# Valve_Driver_V4_1.net
KiCad netlist of a schematic drawn in EAGLE
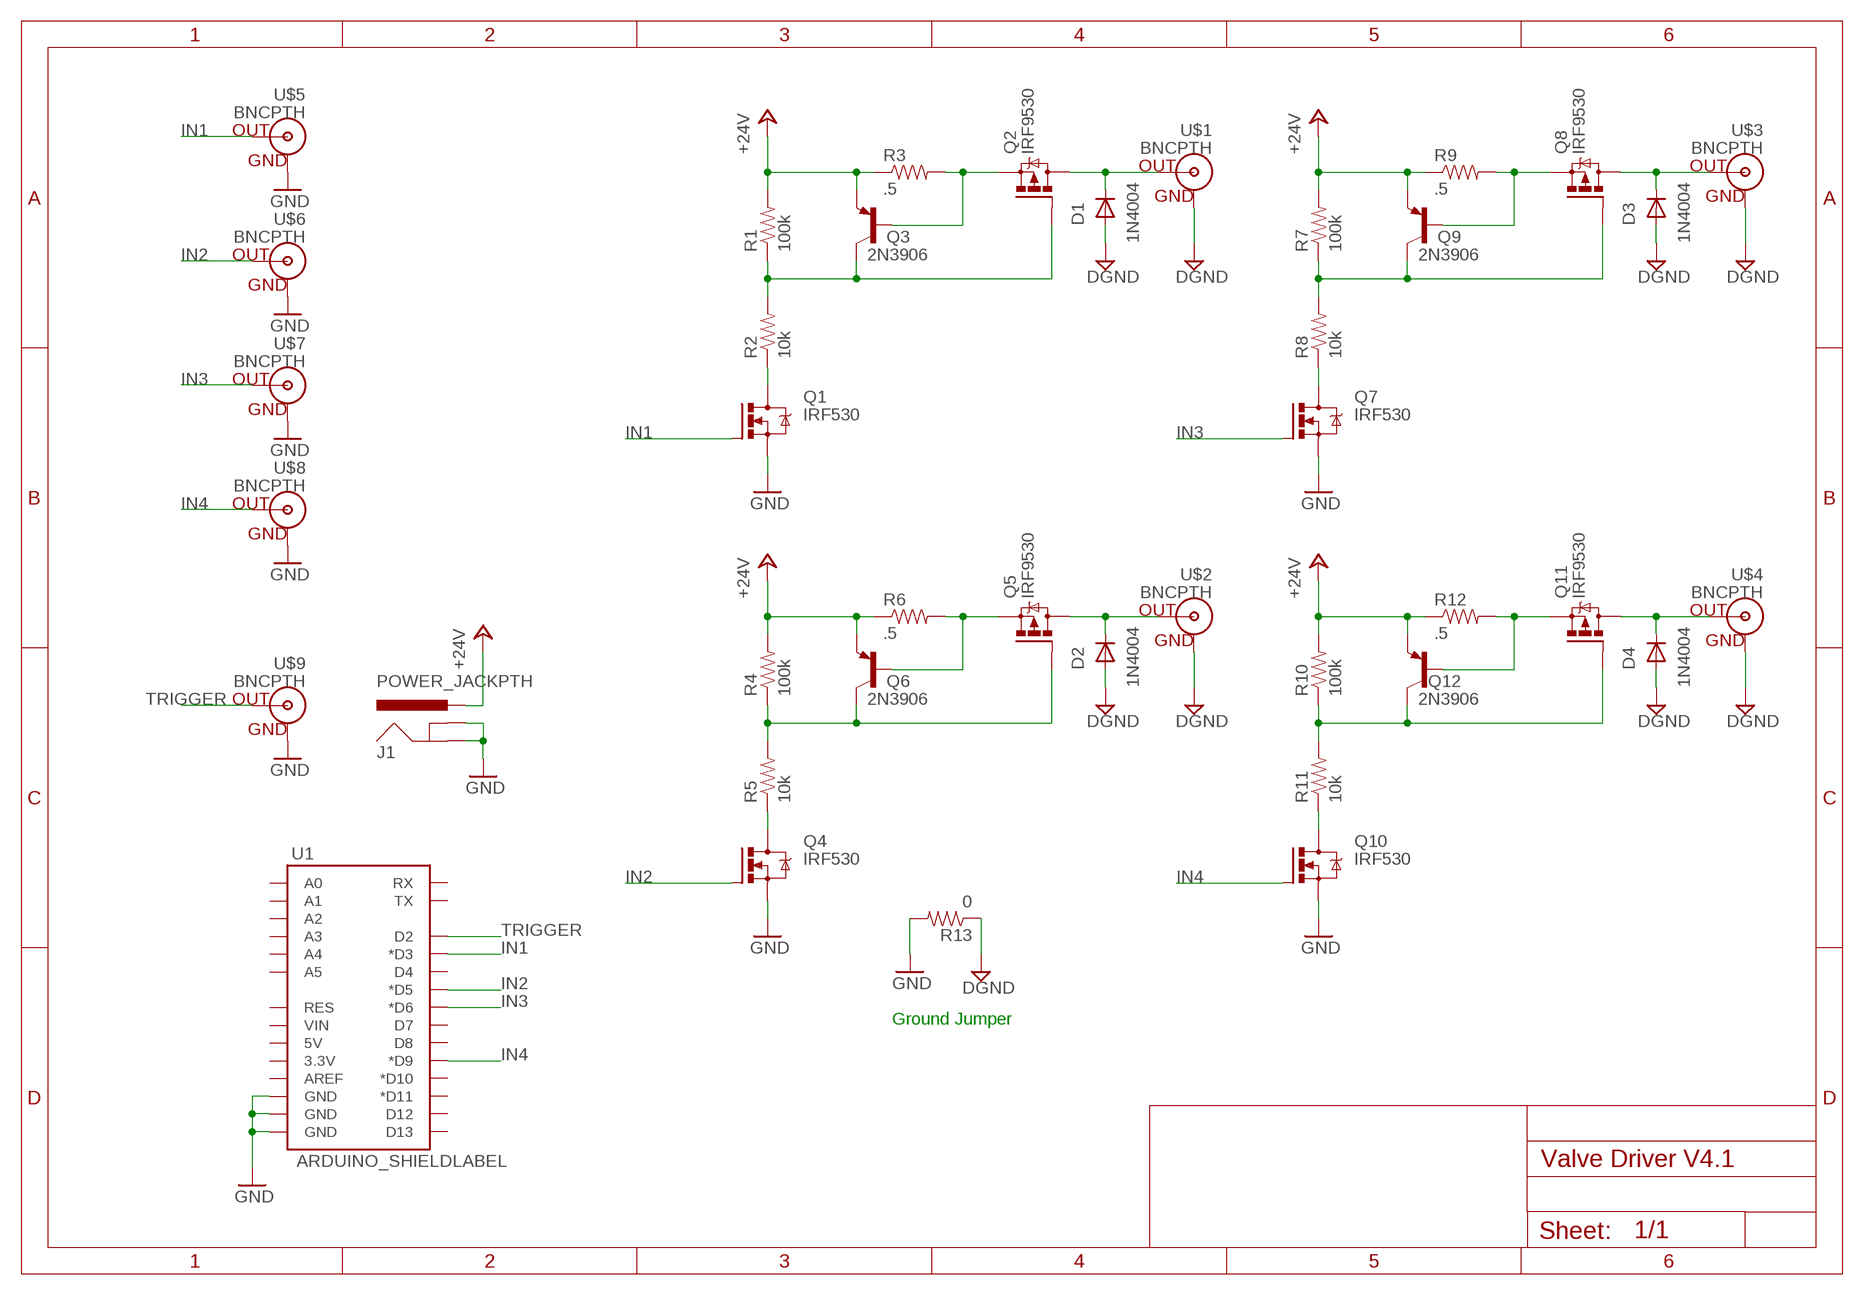
[diagram p0: schematic, sheet 1]

(export (version "E")
  (design (tool "Eeschema 10.0.6"))
  (components
    (comp (ref "D1")
      (value "1N4004")
      (footprint "eagle-import:DO41-10")
      (libsource (lib "eagle-import") (part "1N4004"))
    )
    (comp (ref "D2")
      (value "1N4004")
      (footprint "eagle-import:DO41-10")
      (libsource (lib "eagle-import") (part "1N4004"))
    )
    (comp (ref "D3")
      (value "1N4004")
      (footprint "eagle-import:DO41-10")
      (libsource (lib "eagle-import") (part "1N4004"))
    )
    (comp (ref "D4")
      (value "1N4004")
      (footprint "eagle-import:DO41-10")
      (libsource (lib "eagle-import") (part "1N4004"))
    )
    (comp (ref "J1")
      (value "POWER_JACKPTH")
      (footprint "eagle-import:POWER_JACK_PTH")
      (libsource (lib "eagle-import") (part "POWER_JACKPTH"))
    )
    (comp (ref "Q1")
      (value "IRF530")
      (footprint "eagle-import:TO220BV")
      (libsource (lib "eagle-import") (part "IRF530TO220"))
    )
    (comp (ref "Q2")
      (value "IRF9530")
      (footprint "eagle-import:TO220BV")
      (libsource (lib "eagle-import") (part "IRF9530"))
    )
    (comp (ref "Q3")
      (value "2N3906")
      (footprint "eagle-import:TO92")
      (libsource (lib "eagle-import") (part "2N3906"))
    )
    (comp (ref "Q4")
      (value "IRF530")
      (footprint "eagle-import:TO220BV")
      (libsource (lib "eagle-import") (part "IRF530TO220"))
    )
    (comp (ref "Q5")
      (value "IRF9530")
      (footprint "eagle-import:TO220BV")
      (libsource (lib "eagle-import") (part "IRF9530"))
    )
    (comp (ref "Q6")
      (value "2N3906")
      (footprint "eagle-import:TO92")
      (libsource (lib "eagle-import") (part "2N3906"))
    )
    (comp (ref "Q7")
      (value "IRF530")
      (footprint "eagle-import:TO220BV")
      (libsource (lib "eagle-import") (part "IRF530TO220"))
    )
    (comp (ref "Q8")
      (value "IRF9530")
      (footprint "eagle-import:TO220BV")
      (libsource (lib "eagle-import") (part "IRF9530"))
    )
    (comp (ref "Q9")
      (value "2N3906")
      (footprint "eagle-import:TO92")
      (libsource (lib "eagle-import") (part "2N3906"))
    )
    (comp (ref "Q10")
      (value "IRF530")
      (footprint "eagle-import:TO220BV")
      (libsource (lib "eagle-import") (part "IRF530TO220"))
    )
    (comp (ref "Q11")
      (value "IRF9530")
      (footprint "eagle-import:TO220BV")
      (libsource (lib "eagle-import") (part "IRF9530"))
    )
    (comp (ref "Q12")
      (value "2N3906")
      (footprint "eagle-import:TO92")
      (libsource (lib "eagle-import") (part "2N3906"))
    )
    (comp (ref "R1")
      (value "100k")
      (footprint "eagle-import:AXIAL-0.4")
      (libsource (lib "eagle-import") (part "RESISTORPTH-1/4W"))
    )
    (comp (ref "R2")
      (value "10k")
      (footprint "eagle-import:AXIAL-0.4")
      (libsource (lib "eagle-import") (part "RESISTORPTH-1/4W"))
    )
    (comp (ref "R3")
      (value ".5")
      (footprint "eagle-import:AXIAL-0.4")
      (libsource (lib "eagle-import") (part "RESISTORPTH-1/4W"))
    )
    (comp (ref "R4")
      (value "100k")
      (footprint "eagle-import:AXIAL-0.4")
      (libsource (lib "eagle-import") (part "RESISTORPTH-1/4W"))
    )
    (comp (ref "R5")
      (value "10k")
      (footprint "eagle-import:AXIAL-0.4")
      (libsource (lib "eagle-import") (part "RESISTORPTH-1/4W"))
    )
    (comp (ref "R6")
      (value ".5")
      (footprint "eagle-import:AXIAL-0.4")
      (libsource (lib "eagle-import") (part "RESISTORPTH-1/4W"))
    )
    (comp (ref "R7")
      (value "100k")
      (footprint "eagle-import:AXIAL-0.4")
      (libsource (lib "eagle-import") (part "RESISTORPTH-1/4W"))
    )
    (comp (ref "R8")
      (value "10k")
      (footprint "eagle-import:AXIAL-0.4")
      (libsource (lib "eagle-import") (part "RESISTORPTH-1/4W"))
    )
    (comp (ref "R9")
      (value ".5")
      (footprint "eagle-import:AXIAL-0.4")
      (libsource (lib "eagle-import") (part "RESISTORPTH-1/4W"))
    )
    (comp (ref "R10")
      (value "100k")
      (footprint "eagle-import:AXIAL-0.4")
      (libsource (lib "eagle-import") (part "RESISTORPTH-1/4W"))
    )
    (comp (ref "R11")
      (value "10k")
      (footprint "eagle-import:AXIAL-0.4")
      (libsource (lib "eagle-import") (part "RESISTORPTH-1/4W"))
    )
    (comp (ref "R12")
      (value ".5")
      (footprint "eagle-import:AXIAL-0.4")
      (libsource (lib "eagle-import") (part "RESISTORPTH-1/4W"))
    )
    (comp (ref "R13")
      (value "0")
      (footprint "eagle-import:AXIAL-0.4")
      (libsource (lib "eagle-import") (part "RESISTORPTH-1/4W"))
    )
    (comp (ref "U$1")
      (value "BNCPTH")
      (footprint "eagle-import:BNC")
      (libsource (lib "eagle-import") (part "BNCPTH"))
    )
    (comp (ref "U$2")
      (value "BNCPTH")
      (footprint "eagle-import:BNC")
      (libsource (lib "eagle-import") (part "BNCPTH"))
    )
    (comp (ref "U$3")
      (value "BNCPTH")
      (footprint "eagle-import:BNC")
      (libsource (lib "eagle-import") (part "BNCPTH"))
    )
    (comp (ref "U$4")
      (value "BNCPTH")
      (footprint "eagle-import:BNC")
      (libsource (lib "eagle-import") (part "BNCPTH"))
    )
    (comp (ref "U$5")
      (value "BNCPTH")
      (footprint "eagle-import:BNC")
      (libsource (lib "eagle-import") (part "BNCPTH"))
    )
    (comp (ref "U$6")
      (value "BNCPTH")
      (footprint "eagle-import:BNC")
      (libsource (lib "eagle-import") (part "BNCPTH"))
    )
    (comp (ref "U$7")
      (value "BNCPTH")
      (footprint "eagle-import:BNC")
      (libsource (lib "eagle-import") (part "BNCPTH"))
    )
    (comp (ref "U$8")
      (value "BNCPTH")
      (footprint "eagle-import:BNC")
      (libsource (lib "eagle-import") (part "BNCPTH"))
    )
    (comp (ref "U$9")
      (value "BNCPTH")
      (footprint "eagle-import:BNC")
      (libsource (lib "eagle-import") (part "BNCPTH"))
    )
    (comp (ref "U1")
      (value "ARDUINO_SHIELDLABEL")
      (footprint "eagle-import:DUEMILANOVE_SHIELD")
      (libsource (lib "eagle-import") (part "ARDUINO_SHIELDLABEL"))
    )
  )
  (nets
    (net (code "1") (name "+24V") (class "Default")
      (node (ref "J1") (pin "PWR") (pinfunction "PWR_PWR") (pintype "bidirectional"))
      (node (ref "Q12") (pin "3") (pinfunction "E_3") (pintype "passive"))
      (node (ref "Q3") (pin "3") (pinfunction "E_3") (pintype "passive"))
      (node (ref "Q6") (pin "3") (pinfunction "E_3") (pintype "passive"))
      (node (ref "Q9") (pin "3") (pinfunction "E_3") (pintype "passive"))
      (node (ref "R1") (pin "P$2") (pinfunction "2_P$2") (pintype "passive"))
      (node (ref "R10") (pin "P$2") (pinfunction "2_P$2") (pintype "passive"))
      (node (ref "R12") (pin "P$1") (pinfunction "1_P$1") (pintype "passive"))
      (node (ref "R3") (pin "P$1") (pinfunction "1_P$1") (pintype "passive"))
      (node (ref "R4") (pin "P$2") (pinfunction "2_P$2") (pintype "passive"))
      (node (ref "R6") (pin "P$1") (pinfunction "1_P$1") (pintype "passive"))
      (node (ref "R7") (pin "P$2") (pinfunction "2_P$2") (pintype "passive"))
      (node (ref "R9") (pin "P$1") (pinfunction "1_P$1") (pintype "passive"))
    )
    (net (code "2") (name "/IN1") (class "Default")
      (node (ref "Q1") (pin "G") (pinfunction "G_G") (pintype "passive"))
      (node (ref "U$5") (pin "S") (pinfunction "OUT_S") (pintype "bidirectional"))
      (node (ref "U1") (pin "D3") (pinfunction "*D3_D3") (pintype "bidirectional"))
    )
    (net (code "3") (name "/IN2") (class "Default")
      (node (ref "Q4") (pin "G") (pinfunction "G_G") (pintype "passive"))
      (node (ref "U$6") (pin "S") (pinfunction "OUT_S") (pintype "bidirectional"))
      (node (ref "U1") (pin "D5") (pinfunction "*D5_D5") (pintype "bidirectional"))
    )
    (net (code "4") (name "/IN3") (class "Default")
      (node (ref "Q7") (pin "G") (pinfunction "G_G") (pintype "passive"))
      (node (ref "U$7") (pin "S") (pinfunction "OUT_S") (pintype "bidirectional"))
      (node (ref "U1") (pin "D6") (pinfunction "*D6_D6") (pintype "bidirectional"))
    )
    (net (code "5") (name "/IN4") (class "Default")
      (node (ref "Q10") (pin "G") (pinfunction "G_G") (pintype "passive"))
      (node (ref "U$8") (pin "S") (pinfunction "OUT_S") (pintype "bidirectional"))
      (node (ref "U1") (pin "D9") (pinfunction "*D9_D9") (pintype "bidirectional"))
    )
    (net (code "6") (name "/TRIGGER") (class "Default")
      (node (ref "U$9") (pin "S") (pinfunction "OUT_S") (pintype "bidirectional"))
      (node (ref "U1") (pin "D2") (pinfunction "D2_D2") (pintype "bidirectional"))
    )
    (net (code "7") (name "DGND") (class "Default")
      (node (ref "D1") (pin "A") (pinfunction "A_A") (pintype "passive"))
      (node (ref "D2") (pin "A") (pinfunction "A_A") (pintype "passive"))
      (node (ref "D3") (pin "A") (pinfunction "A_A") (pintype "passive"))
      (node (ref "D4") (pin "A") (pinfunction "A_A") (pintype "passive"))
      (node (ref "R13") (pin "P$1") (pinfunction "1_P$1") (pintype "passive"))
      (node (ref "U$1") (pin "GND") (pinfunction "GND_GND") (pintype "bidirectional"))
      (node (ref "U$2") (pin "GND") (pinfunction "GND_GND") (pintype "bidirectional"))
      (node (ref "U$3") (pin "GND") (pinfunction "GND_GND") (pintype "bidirectional"))
      (node (ref "U$4") (pin "GND") (pinfunction "GND_GND") (pintype "bidirectional"))
    )
    (net (code "8") (name "GND") (class "Default")
      (node (ref "J1") (pin "GND") (pinfunction "GND_GND") (pintype "bidirectional"))
      (node (ref "J1") (pin "GNDBREAK") (pinfunction "GNDBREAK_GNDBREAK") (pintype "bidirectional"))
      (node (ref "Q1") (pin "S") (pinfunction "S_S") (pintype "passive"))
      (node (ref "Q10") (pin "S") (pinfunction "S_S") (pintype "passive"))
      (node (ref "Q4") (pin "S") (pinfunction "S_S") (pintype "passive"))
      (node (ref "Q7") (pin "S") (pinfunction "S_S") (pintype "passive"))
      (node (ref "R13") (pin "P$2") (pinfunction "2_P$2") (pintype "passive"))
      (node (ref "U$5") (pin "GND") (pinfunction "GND_GND") (pintype "bidirectional"))
      (node (ref "U$6") (pin "GND") (pinfunction "GND_GND") (pintype "bidirectional"))
      (node (ref "U$7") (pin "GND") (pinfunction "GND_GND") (pintype "bidirectional"))
      (node (ref "U$8") (pin "GND") (pinfunction "GND_GND") (pintype "bidirectional"))
      (node (ref "U$9") (pin "GND") (pinfunction "GND_GND") (pintype "bidirectional"))
      (node (ref "U1") (pin "GND@0") (pinfunction "GND_GND@0") (pintype "bidirectional"))
      (node (ref "U1") (pin "GND@1") (pinfunction "GND_GND@1") (pintype "bidirectional"))
      (node (ref "U1") (pin "GND@2") (pinfunction "GND_GND@2") (pintype "bidirectional"))
    )
    (net (code "9") (name "Net-(Q3-B)") (class "Default")
      (node (ref "Q2") (pin "S") (pinfunction "S_S") (pintype "passive"))
      (node (ref "Q3") (pin "2") (pinfunction "B_2") (pintype "passive"))
      (node (ref "R3") (pin "P$2") (pinfunction "2_P$2") (pintype "passive"))
    )
    (net (code "10") (name "Net-(Q3-C)") (class "Default")
      (node (ref "Q2") (pin "G") (pinfunction "G_G") (pintype "passive"))
      (node (ref "Q3") (pin "1") (pinfunction "C_1") (pintype "passive"))
      (node (ref "R1") (pin "P$1") (pinfunction "1_P$1") (pintype "passive"))
      (node (ref "R2") (pin "P$2") (pinfunction "2_P$2") (pintype "passive"))
    )
    (net (code "11") (name "Net-(Q6-B)") (class "Default")
      (node (ref "Q5") (pin "S") (pinfunction "S_S") (pintype "passive"))
      (node (ref "Q6") (pin "2") (pinfunction "B_2") (pintype "passive"))
      (node (ref "R6") (pin "P$2") (pinfunction "2_P$2") (pintype "passive"))
    )
    (net (code "12") (name "Net-(Q6-C)") (class "Default")
      (node (ref "Q5") (pin "G") (pinfunction "G_G") (pintype "passive"))
      (node (ref "Q6") (pin "1") (pinfunction "C_1") (pintype "passive"))
      (node (ref "R4") (pin "P$1") (pinfunction "1_P$1") (pintype "passive"))
      (node (ref "R5") (pin "P$2") (pinfunction "2_P$2") (pintype "passive"))
    )
    (net (code "13") (name "Net-(Q9-B)") (class "Default")
      (node (ref "Q8") (pin "S") (pinfunction "S_S") (pintype "passive"))
      (node (ref "Q9") (pin "2") (pinfunction "B_2") (pintype "passive"))
      (node (ref "R9") (pin "P$2") (pinfunction "2_P$2") (pintype "passive"))
    )
    (net (code "14") (name "Net-(Q9-C)") (class "Default")
      (node (ref "Q8") (pin "G") (pinfunction "G_G") (pintype "passive"))
      (node (ref "Q9") (pin "1") (pinfunction "C_1") (pintype "passive"))
      (node (ref "R7") (pin "P$1") (pinfunction "1_P$1") (pintype "passive"))
      (node (ref "R8") (pin "P$2") (pinfunction "2_P$2") (pintype "passive"))
    )
    (net (code "15") (name "Net-(Q12-B)") (class "Default")
      (node (ref "Q11") (pin "S") (pinfunction "S_S") (pintype "passive"))
      (node (ref "Q12") (pin "2") (pinfunction "B_2") (pintype "passive"))
      (node (ref "R12") (pin "P$2") (pinfunction "2_P$2") (pintype "passive"))
    )
    (net (code "16") (name "Net-(Q12-C)") (class "Default")
      (node (ref "Q11") (pin "G") (pinfunction "G_G") (pintype "passive"))
      (node (ref "Q12") (pin "1") (pinfunction "C_1") (pintype "passive"))
      (node (ref "R10") (pin "P$1") (pinfunction "1_P$1") (pintype "passive"))
      (node (ref "R11") (pin "P$2") (pinfunction "2_P$2") (pintype "passive"))
    )
    (net (code "17") (name "Net-(R2-1)") (class "Default")
      (node (ref "Q1") (pin "D") (pinfunction "D_D") (pintype "passive"))
      (node (ref "R2") (pin "P$1") (pinfunction "1_P$1") (pintype "passive"))
    )
    (net (code "18") (name "Net-(R5-1)") (class "Default")
      (node (ref "Q4") (pin "D") (pinfunction "D_D") (pintype "passive"))
      (node (ref "R5") (pin "P$1") (pinfunction "1_P$1") (pintype "passive"))
    )
    (net (code "19") (name "Net-(R8-1)") (class "Default")
      (node (ref "Q7") (pin "D") (pinfunction "D_D") (pintype "passive"))
      (node (ref "R8") (pin "P$1") (pinfunction "1_P$1") (pintype "passive"))
    )
    (net (code "20") (name "Net-(R11-1)") (class "Default")
      (node (ref "Q10") (pin "D") (pinfunction "D_D") (pintype "passive"))
      (node (ref "R11") (pin "P$1") (pinfunction "1_P$1") (pintype "passive"))
    )
    (net (code "21") (name "Net-(U$1-OUT)") (class "Default")
      (node (ref "D1") (pin "C") (pinfunction "C_C") (pintype "passive"))
      (node (ref "Q2") (pin "D") (pinfunction "D_D") (pintype "passive"))
      (node (ref "U$1") (pin "S") (pinfunction "OUT_S") (pintype "bidirectional"))
    )
    (net (code "22") (name "Net-(U$2-OUT)") (class "Default")
      (node (ref "D2") (pin "C") (pinfunction "C_C") (pintype "passive"))
      (node (ref "Q5") (pin "D") (pinfunction "D_D") (pintype "passive"))
      (node (ref "U$2") (pin "S") (pinfunction "OUT_S") (pintype "bidirectional"))
    )
    (net (code "23") (name "Net-(U$3-OUT)") (class "Default")
      (node (ref "D3") (pin "C") (pinfunction "C_C") (pintype "passive"))
      (node (ref "Q8") (pin "D") (pinfunction "D_D") (pintype "passive"))
      (node (ref "U$3") (pin "S") (pinfunction "OUT_S") (pintype "bidirectional"))
    )
    (net (code "24") (name "Net-(U$4-OUT)") (class "Default")
      (node (ref "D4") (pin "C") (pinfunction "C_C") (pintype "passive"))
      (node (ref "Q11") (pin "D") (pinfunction "D_D") (pintype "passive"))
      (node (ref "U$4") (pin "S") (pinfunction "OUT_S") (pintype "bidirectional"))
    )
    (net (code "25") (name "unconnected-(U1-*D10-PadD10)") (class "Default")
      (node (ref "U1") (pin "D10") (pinfunction "*D10_D10") (pintype "bidirectional"))
    )
    (net (code "26") (name "unconnected-(U1-*D11-PadD11)") (class "Default")
      (node (ref "U1") (pin "D11") (pinfunction "*D11_D11") (pintype "bidirectional"))
    )
    (net (code "27") (name "unconnected-(U1-Pad3.3V)") (class "Default")
      (node (ref "U1") (pin "3.3V") (pinfunction "3.3V_3.3V") (pintype "bidirectional"))
    )
    (net (code "28") (name "unconnected-(U1-Pad5V)") (class "Default")
      (node (ref "U1") (pin "5V") (pinfunction "5V_5V") (pintype "bidirectional"))
    )
    (net (code "29") (name "unconnected-(U1-PadA0)") (class "Default")
      (node (ref "U1") (pin "A0") (pinfunction "A0_A0") (pintype "bidirectional"))
    )
    (net (code "30") (name "unconnected-(U1-PadA1)") (class "Default")
      (node (ref "U1") (pin "A1") (pinfunction "A1_A1") (pintype "bidirectional"))
    )
    (net (code "31") (name "unconnected-(U1-PadA2)") (class "Default")
      (node (ref "U1") (pin "A2") (pinfunction "A2_A2") (pintype "bidirectional"))
    )
    (net (code "32") (name "unconnected-(U1-PadA3)") (class "Default")
      (node (ref "U1") (pin "A3") (pinfunction "A3_A3") (pintype "bidirectional"))
    )
    (net (code "33") (name "unconnected-(U1-PadA4)") (class "Default")
      (node (ref "U1") (pin "A4") (pinfunction "A4_A4") (pintype "bidirectional"))
    )
    (net (code "34") (name "unconnected-(U1-PadA5)") (class "Default")
      (node (ref "U1") (pin "A5") (pinfunction "A5_A5") (pintype "bidirectional"))
    )
    (net (code "35") (name "unconnected-(U1-PadAREF)") (class "Default")
      (node (ref "U1") (pin "AREF") (pinfunction "AREF_AREF") (pintype "bidirectional"))
    )
    (net (code "36") (name "unconnected-(U1-PadD4)") (class "Default")
      (node (ref "U1") (pin "D4") (pinfunction "D4_D4") (pintype "bidirectional"))
    )
    (net (code "37") (name "unconnected-(U1-PadD7)") (class "Default")
      (node (ref "U1") (pin "D7") (pinfunction "D7_D7") (pintype "bidirectional"))
    )
    (net (code "38") (name "unconnected-(U1-PadD8)") (class "Default")
      (node (ref "U1") (pin "D8") (pinfunction "D8_D8") (pintype "bidirectional"))
    )
    (net (code "39") (name "unconnected-(U1-PadD12)") (class "Default")
      (node (ref "U1") (pin "D12") (pinfunction "D12_D12") (pintype "bidirectional"))
    )
    (net (code "40") (name "unconnected-(U1-PadD13)") (class "Default")
      (node (ref "U1") (pin "D13") (pinfunction "D13_D13") (pintype "bidirectional"))
    )
    (net (code "41") (name "unconnected-(U1-PadRES)") (class "Default")
      (node (ref "U1") (pin "RES") (pinfunction "RES_RES") (pintype "bidirectional"))
    )
    (net (code "42") (name "unconnected-(U1-PadRX)") (class "Default")
      (node (ref "U1") (pin "RX") (pinfunction "RX_RX") (pintype "bidirectional"))
    )
    (net (code "43") (name "unconnected-(U1-PadTX)") (class "Default")
      (node (ref "U1") (pin "TX") (pinfunction "TX_TX") (pintype "bidirectional"))
    )
    (net (code "44") (name "unconnected-(U1-PadVIN)") (class "Default")
      (node (ref "U1") (pin "VIN") (pinfunction "VIN_VIN") (pintype "bidirectional"))
    )
  )
)
